# Dram.net
KiCad netlist of a schematic drawn in EAGLE
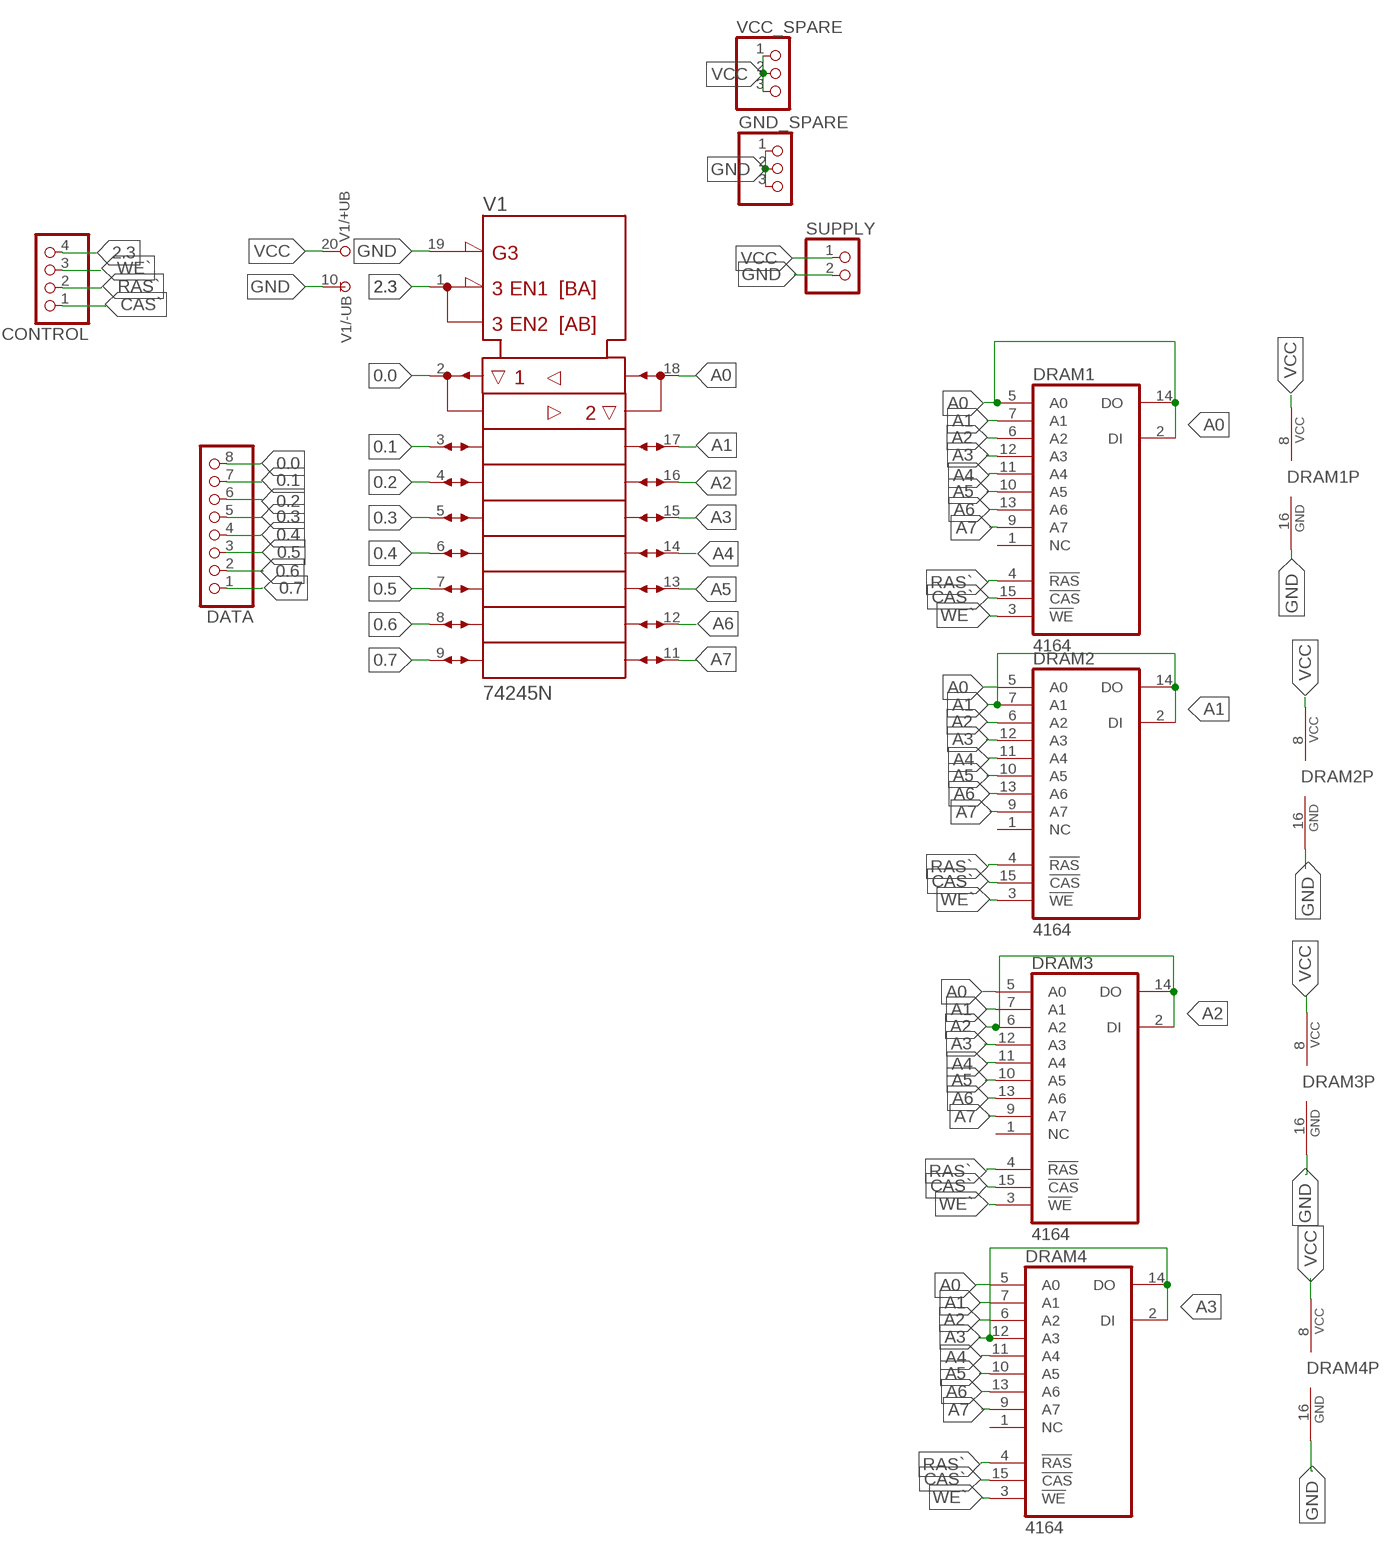
[diagram p0: schematic, sheet 1]

(export (version "E")
  (design (tool "Eeschema 10.0.6"))
  (components
    (comp (ref "CONTROL")
      (value "PINHD-1X4")
      (footprint "eagle-import:1X04")
      (libsource (lib "eagle-import") (part "PINHD-1X4"))
    )
    (comp (ref "DATA")
      (value "PINHD-1X8")
      (footprint "eagle-import:1X08")
      (libsource (lib "eagle-import") (part "PINHD-1X8"))
    )
    (comp (ref "DRAM1")
      (value "4164")
      (footprint "eagle-import:DIP762W53P254L1969H508Q16B")
      (libsource (lib "eagle-import") (part "4164"))
    )
    (comp (ref "DRAM2")
      (value "4164")
      (footprint "eagle-import:DIP762W53P254L1969H508Q16B")
      (libsource (lib "eagle-import") (part "4164"))
    )
    (comp (ref "DRAM3")
      (value "4164")
      (footprint "eagle-import:DIP762W53P254L1969H508Q16B")
      (libsource (lib "eagle-import") (part "4164"))
    )
    (comp (ref "DRAM4")
      (value "4164")
      (footprint "eagle-import:DIP762W53P254L1969H508Q16B")
      (libsource (lib "eagle-import") (part "4164"))
    )
    (comp (ref "GND_SPARE")
      (value "PINHD-1X3")
      (footprint "eagle-import:1X03")
      (libsource (lib "eagle-import") (part "PINHD-1X3"))
    )
    (comp (ref "SUPPLY")
      (value "PINHD-1X2")
      (footprint "eagle-import:1X02")
      (libsource (lib "eagle-import") (part "PINHD-1X2"))
    )
    (comp (ref "V1")
      (value "74245N")
      (footprint "eagle-import:DIL20")
      (libsource (lib "eagle-import") (part "74245N"))
    )
    (comp (ref "VCC_SPARE")
      (value "PINHD-1X3")
      (footprint "eagle-import:1X03")
      (libsource (lib "eagle-import") (part "PINHD-1X3"))
    )
  )
  (nets
    (net (code "1") (name "0.0") (class "Default")
      (node (ref "DATA") (pin "8") (pinfunction "8_8") (pintype "passive"))
      (node (ref "V1") (pin "2") (pinfunction "A1_2") (pintype "bidirectional"))
    )
    (net (code "2") (name "0.1") (class "Default")
      (node (ref "DATA") (pin "7") (pinfunction "7_7") (pintype "passive"))
      (node (ref "V1") (pin "3") (pinfunction "A2_3") (pintype "bidirectional"))
    )
    (net (code "3") (name "0.2") (class "Default")
      (node (ref "DATA") (pin "6") (pinfunction "6_6") (pintype "passive"))
      (node (ref "V1") (pin "4") (pinfunction "A3_4") (pintype "bidirectional"))
    )
    (net (code "4") (name "0.3") (class "Default")
      (node (ref "DATA") (pin "5") (pinfunction "5_5") (pintype "passive"))
      (node (ref "V1") (pin "5") (pinfunction "A4_5") (pintype "bidirectional"))
    )
    (net (code "5") (name "0.4") (class "Default")
      (node (ref "DATA") (pin "4") (pinfunction "4_4") (pintype "passive"))
      (node (ref "V1") (pin "6") (pinfunction "A5_6") (pintype "bidirectional"))
    )
    (net (code "6") (name "0.5") (class "Default")
      (node (ref "DATA") (pin "3") (pinfunction "3_3") (pintype "passive"))
      (node (ref "V1") (pin "7") (pinfunction "A6_7") (pintype "bidirectional"))
    )
    (net (code "7") (name "0.6") (class "Default")
      (node (ref "DATA") (pin "2") (pinfunction "2_2") (pintype "passive"))
      (node (ref "V1") (pin "8") (pinfunction "A7_8") (pintype "bidirectional"))
    )
    (net (code "8") (name "0.7") (class "Default")
      (node (ref "DATA") (pin "1") (pinfunction "1_1") (pintype "passive"))
      (node (ref "V1") (pin "9") (pinfunction "A8_9") (pintype "bidirectional"))
    )
    (net (code "9") (name "2.3") (class "Default")
      (node (ref "CONTROL") (pin "4") (pinfunction "4_4") (pintype "passive"))
      (node (ref "V1") (pin "1") (pinfunction "DIR_1") (pintype "input"))
    )
    (net (code "10") (name "A0") (class "Default")
      (node (ref "DRAM1") (pin "14") (pinfunction "DO_14") (pintype "tri_state"))
      (node (ref "DRAM1") (pin "2") (pinfunction "DI_2") (pintype "input"))
      (node (ref "DRAM1") (pin "5") (pinfunction "A0_5") (pintype "input"))
      (node (ref "DRAM2") (pin "5") (pinfunction "A0_5") (pintype "input"))
      (node (ref "DRAM3") (pin "5") (pinfunction "A0_5") (pintype "input"))
      (node (ref "DRAM4") (pin "5") (pinfunction "A0_5") (pintype "input"))
      (node (ref "V1") (pin "18") (pinfunction "B1_18") (pintype "bidirectional"))
    )
    (net (code "11") (name "A1") (class "Default")
      (node (ref "DRAM1") (pin "7") (pinfunction "A1_7") (pintype "input"))
      (node (ref "DRAM2") (pin "14") (pinfunction "DO_14") (pintype "tri_state"))
      (node (ref "DRAM2") (pin "2") (pinfunction "DI_2") (pintype "input"))
      (node (ref "DRAM2") (pin "7") (pinfunction "A1_7") (pintype "input"))
      (node (ref "DRAM3") (pin "7") (pinfunction "A1_7") (pintype "input"))
      (node (ref "DRAM4") (pin "7") (pinfunction "A1_7") (pintype "input"))
      (node (ref "V1") (pin "17") (pinfunction "B2_17") (pintype "bidirectional"))
    )
    (net (code "12") (name "A2") (class "Default")
      (node (ref "DRAM1") (pin "6") (pinfunction "A2_6") (pintype "input"))
      (node (ref "DRAM2") (pin "6") (pinfunction "A2_6") (pintype "input"))
      (node (ref "DRAM3") (pin "14") (pinfunction "DO_14") (pintype "tri_state"))
      (node (ref "DRAM3") (pin "2") (pinfunction "DI_2") (pintype "input"))
      (node (ref "DRAM3") (pin "6") (pinfunction "A2_6") (pintype "input"))
      (node (ref "DRAM4") (pin "6") (pinfunction "A2_6") (pintype "input"))
      (node (ref "V1") (pin "16") (pinfunction "B3_16") (pintype "bidirectional"))
    )
    (net (code "13") (name "A3") (class "Default")
      (node (ref "DRAM1") (pin "12") (pinfunction "A3_12") (pintype "input"))
      (node (ref "DRAM2") (pin "12") (pinfunction "A3_12") (pintype "input"))
      (node (ref "DRAM3") (pin "12") (pinfunction "A3_12") (pintype "input"))
      (node (ref "DRAM4") (pin "12") (pinfunction "A3_12") (pintype "input"))
      (node (ref "DRAM4") (pin "14") (pinfunction "DO_14") (pintype "tri_state"))
      (node (ref "DRAM4") (pin "2") (pinfunction "DI_2") (pintype "input"))
      (node (ref "V1") (pin "15") (pinfunction "B4_15") (pintype "bidirectional"))
    )
    (net (code "14") (name "A4") (class "Default")
      (node (ref "DRAM1") (pin "11") (pinfunction "A4_11") (pintype "input"))
      (node (ref "DRAM2") (pin "11") (pinfunction "A4_11") (pintype "input"))
      (node (ref "DRAM3") (pin "11") (pinfunction "A4_11") (pintype "input"))
      (node (ref "DRAM4") (pin "11") (pinfunction "A4_11") (pintype "input"))
      (node (ref "V1") (pin "14") (pinfunction "B5_14") (pintype "bidirectional"))
    )
    (net (code "15") (name "A5") (class "Default")
      (node (ref "DRAM1") (pin "10") (pinfunction "A5_10") (pintype "input"))
      (node (ref "DRAM2") (pin "10") (pinfunction "A5_10") (pintype "input"))
      (node (ref "DRAM3") (pin "10") (pinfunction "A5_10") (pintype "input"))
      (node (ref "DRAM4") (pin "10") (pinfunction "A5_10") (pintype "input"))
      (node (ref "V1") (pin "13") (pinfunction "B6_13") (pintype "bidirectional"))
    )
    (net (code "16") (name "A6") (class "Default")
      (node (ref "DRAM1") (pin "13") (pinfunction "A6_13") (pintype "input"))
      (node (ref "DRAM2") (pin "13") (pinfunction "A6_13") (pintype "input"))
      (node (ref "DRAM3") (pin "13") (pinfunction "A6_13") (pintype "input"))
      (node (ref "DRAM4") (pin "13") (pinfunction "A6_13") (pintype "input"))
      (node (ref "V1") (pin "12") (pinfunction "B7_12") (pintype "bidirectional"))
    )
    (net (code "17") (name "A7") (class "Default")
      (node (ref "DRAM1") (pin "9") (pinfunction "A7_9") (pintype "input"))
      (node (ref "DRAM2") (pin "9") (pinfunction "A7_9") (pintype "input"))
      (node (ref "DRAM3") (pin "9") (pinfunction "A7_9") (pintype "input"))
      (node (ref "DRAM4") (pin "9") (pinfunction "A7_9") (pintype "input"))
      (node (ref "V1") (pin "11") (pinfunction "B8_11") (pintype "bidirectional"))
    )
    (net (code "18") (name "CAS`") (class "Default")
      (node (ref "CONTROL") (pin "1") (pinfunction "1_1") (pintype "passive"))
      (node (ref "DRAM1") (pin "15") (pinfunction "~{CAS}_15") (pintype "input"))
      (node (ref "DRAM2") (pin "15") (pinfunction "~{CAS}_15") (pintype "input"))
      (node (ref "DRAM3") (pin "15") (pinfunction "~{CAS}_15") (pintype "input"))
      (node (ref "DRAM4") (pin "15") (pinfunction "~{CAS}_15") (pintype "input"))
    )
    (net (code "19") (name "GND") (class "Default")
      (node (ref "DRAM1") (pin "16") (pinfunction "GND_16") (pintype "power_in"))
      (node (ref "DRAM2") (pin "16") (pinfunction "GND_16") (pintype "power_in"))
      (node (ref "DRAM3") (pin "16") (pinfunction "GND_16") (pintype "power_in"))
      (node (ref "DRAM4") (pin "16") (pinfunction "GND_16") (pintype "power_in"))
      (node (ref "GND_SPARE") (pin "1") (pinfunction "1_1") (pintype "passive"))
      (node (ref "GND_SPARE") (pin "2") (pinfunction "2_2") (pintype "passive"))
      (node (ref "GND_SPARE") (pin "3") (pinfunction "3_3") (pintype "passive"))
      (node (ref "SUPPLY") (pin "2") (pinfunction "2_2") (pintype "passive"))
      (node (ref "V1") (pin "10") (pinfunction "-UB_10") (pintype "power_in"))
      (node (ref "V1") (pin "19") (pinfunction "~{G}_19") (pintype "input"))
    )
    (net (code "20") (name "RAS`") (class "Default")
      (node (ref "CONTROL") (pin "2") (pinfunction "2_2") (pintype "passive"))
      (node (ref "DRAM1") (pin "4") (pinfunction "~{RAS}_4") (pintype "input"))
      (node (ref "DRAM2") (pin "4") (pinfunction "~{RAS}_4") (pintype "input"))
      (node (ref "DRAM3") (pin "4") (pinfunction "~{RAS}_4") (pintype "input"))
      (node (ref "DRAM4") (pin "4") (pinfunction "~{RAS}_4") (pintype "input"))
    )
    (net (code "21") (name "VCC") (class "Default")
      (node (ref "DRAM1") (pin "8") (pinfunction "VCC_8") (pintype "power_in"))
      (node (ref "DRAM2") (pin "8") (pinfunction "VCC_8") (pintype "power_in"))
      (node (ref "DRAM3") (pin "8") (pinfunction "VCC_8") (pintype "power_in"))
      (node (ref "DRAM4") (pin "8") (pinfunction "VCC_8") (pintype "power_in"))
      (node (ref "SUPPLY") (pin "1") (pinfunction "1_1") (pintype "passive"))
      (node (ref "V1") (pin "20") (pinfunction "+UB_20") (pintype "power_in"))
      (node (ref "VCC_SPARE") (pin "1") (pinfunction "1_1") (pintype "passive"))
      (node (ref "VCC_SPARE") (pin "2") (pinfunction "2_2") (pintype "passive"))
      (node (ref "VCC_SPARE") (pin "3") (pinfunction "3_3") (pintype "passive"))
    )
    (net (code "22") (name "WE`") (class "Default")
      (node (ref "CONTROL") (pin "3") (pinfunction "3_3") (pintype "passive"))
      (node (ref "DRAM1") (pin "3") (pinfunction "~{WE}_3") (pintype "input"))
      (node (ref "DRAM2") (pin "3") (pinfunction "~{WE}_3") (pintype "input"))
      (node (ref "DRAM3") (pin "3") (pinfunction "~{WE}_3") (pintype "input"))
      (node (ref "DRAM4") (pin "3") (pinfunction "~{WE}_3") (pintype "input"))
    )
    (net (code "23") (name "unconnected-(DRAM1A-NC-Pad1)") (class "Default")
      (node (ref "DRAM1") (pin "1") (pinfunction "NC_1") (pintype "passive"))
    )
    (net (code "24") (name "unconnected-(DRAM2A-NC-Pad1)") (class "Default")
      (node (ref "DRAM2") (pin "1") (pinfunction "NC_1") (pintype "passive"))
    )
    (net (code "25") (name "unconnected-(DRAM3A-NC-Pad1)") (class "Default")
      (node (ref "DRAM3") (pin "1") (pinfunction "NC_1") (pintype "passive"))
    )
    (net (code "26") (name "unconnected-(DRAM4A-NC-Pad1)") (class "Default")
      (node (ref "DRAM4") (pin "1") (pinfunction "NC_1") (pintype "passive"))
    )
  )
)
